# BMX055.net
KiCad netlist of a schematic drawn in EAGLE
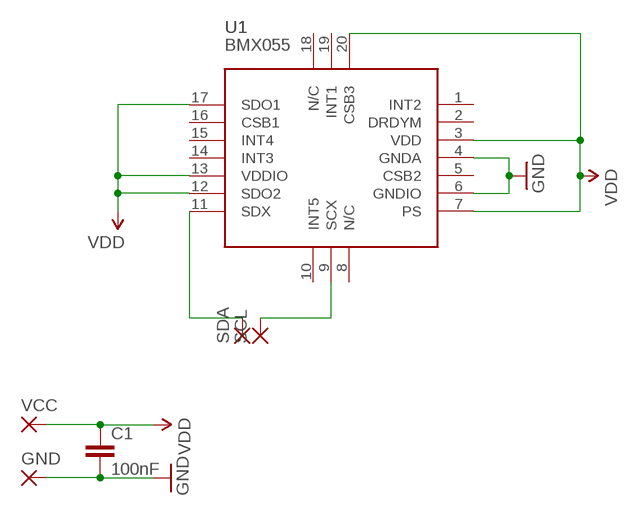
[diagram p0: schematic, sheet 1]

(export (version "E")
  (design (tool "Eeschema 10.0.6"))
  (components
    (comp (ref "C1")
      (value "100nF")
      (footprint "eagle-import:1206")
      (libsource (lib "eagle-import") (part "CAP1206"))
    )
    (comp (ref "GND")
      (value "SMD2")
      (footprint "eagle-import:SMD1,27-2,54")
      (libsource (lib "eagle-import") (part "SMD2"))
    )
    (comp (ref "SCL")
      (value "SMD2")
      (footprint "eagle-import:SMD1,27-2,54")
      (libsource (lib "eagle-import") (part "SMD2"))
    )
    (comp (ref "SDA")
      (value "SMD2")
      (footprint "eagle-import:SMD1,27-2,54")
      (libsource (lib "eagle-import") (part "SMD2"))
    )
    (comp (ref "U1")
      (value "BMX055")
      (footprint "eagle-import:BMX055")
      (libsource (lib "eagle-import") (part "BMX055"))
    )
    (comp (ref "VCC")
      (value "SMD2")
      (footprint "eagle-import:SMD1,27-2,54")
      (libsource (lib "eagle-import") (part "SMD2"))
    )
  )
  (nets
    (net (code "1") (name "GND") (class "Default")
      (node (ref "C1") (pin "2") (pinfunction "2_2") (pintype "passive"))
      (node (ref "GND") (pin "1") (pinfunction "P_1") (pintype "passive"))
      (node (ref "U1") (pin "4") (pinfunction "GNDA_4") (pintype "bidirectional"))
      (node (ref "U1") (pin "6") (pinfunction "GNDIO_6") (pintype "bidirectional"))
    )
    (net (code "2") (name "Net-(SCL-P)") (class "Default")
      (node (ref "SCL") (pin "1") (pinfunction "P_1") (pintype "passive"))
      (node (ref "U1") (pin "9") (pinfunction "SCX_9") (pintype "bidirectional"))
    )
    (net (code "3") (name "Net-(SDA-P)") (class "Default")
      (node (ref "SDA") (pin "1") (pinfunction "P_1") (pintype "passive"))
      (node (ref "U1") (pin "11") (pinfunction "SDX_11") (pintype "bidirectional"))
    )
    (net (code "4") (name "VDD") (class "Default")
      (node (ref "C1") (pin "1") (pinfunction "1_1") (pintype "passive"))
      (node (ref "U1") (pin "12") (pinfunction "SDO2_12") (pintype "bidirectional"))
      (node (ref "U1") (pin "13") (pinfunction "VDDIO_13") (pintype "bidirectional"))
      (node (ref "U1") (pin "17") (pinfunction "SDO1_17") (pintype "bidirectional"))
      (node (ref "U1") (pin "20") (pinfunction "CSB3_20") (pintype "bidirectional"))
      (node (ref "U1") (pin "3") (pinfunction "VDD_3") (pintype "bidirectional"))
      (node (ref "U1") (pin "7") (pinfunction "PS_7") (pintype "bidirectional"))
      (node (ref "VCC") (pin "1") (pinfunction "P_1") (pintype "passive"))
    )
    (net (code "5") (name "unconnected-(U1-CSB1-Pad16)") (class "Default")
      (node (ref "U1") (pin "16") (pinfunction "CSB1_16") (pintype "bidirectional"))
    )
    (net (code "6") (name "unconnected-(U1-CSB2-Pad5)") (class "Default")
      (node (ref "U1") (pin "5") (pinfunction "CSB2_5") (pintype "bidirectional"))
    )
    (net (code "7") (name "unconnected-(U1-DRDYM-Pad2)") (class "Default")
      (node (ref "U1") (pin "2") (pinfunction "DRDYM_2") (pintype "bidirectional"))
    )
    (net (code "8") (name "unconnected-(U1-INT1-Pad19)") (class "Default")
      (node (ref "U1") (pin "19") (pinfunction "INT1_19") (pintype "bidirectional"))
    )
    (net (code "9") (name "unconnected-(U1-INT2-Pad1)") (class "Default")
      (node (ref "U1") (pin "1") (pinfunction "INT2_1") (pintype "bidirectional"))
    )
    (net (code "10") (name "unconnected-(U1-INT3-Pad14)") (class "Default")
      (node (ref "U1") (pin "14") (pinfunction "INT3_14") (pintype "bidirectional"))
    )
    (net (code "11") (name "unconnected-(U1-INT4-Pad15)") (class "Default")
      (node (ref "U1") (pin "15") (pinfunction "INT4_15") (pintype "bidirectional"))
    )
    (net (code "12") (name "unconnected-(U1-INT5-Pad10)") (class "Default")
      (node (ref "U1") (pin "10") (pinfunction "INT5_10") (pintype "bidirectional"))
    )
    (net (code "13") (name "unconnected-(U1-N{slash}C-Pad8)") (class "Default")
      (node (ref "U1") (pin "8") (pinfunction "N/C_8") (pintype "bidirectional"))
    )
    (net (code "14") (name "unconnected-(U1-N{slash}C-Pad18)") (class "Default")
      (node (ref "U1") (pin "18") (pinfunction "N/C_18") (pintype "bidirectional"))
    )
  )
)
